# adapter.net
KiCad netlist of a schematic drawn in EAGLE
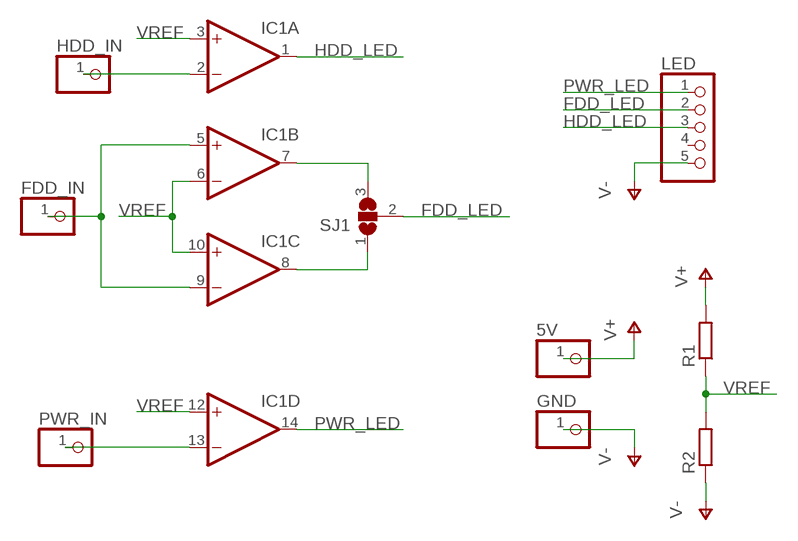
[diagram p0: schematic, sheet 1]

(export (version "E")
  (design (tool "Eeschema 10.0.6"))
  (components
    (comp (ref "5V")
      (value "PINHD-1X1")
      (footprint "eagle-import:1X01")
      (libsource (lib "eagle-import") (part "PINHD-1X1"))
    )
    (comp (ref "FDD_IN")
      (value "PINHD-1X1")
      (footprint "eagle-import:1X01")
      (libsource (lib "eagle-import") (part "PINHD-1X1"))
    )
    (comp (ref "GND")
      (value "PINHD-1X1")
      (footprint "eagle-import:1X01")
      (libsource (lib "eagle-import") (part "PINHD-1X1"))
    )
    (comp (ref "HDD_IN")
      (value "PINHD-1X1")
      (footprint "eagle-import:1X01")
      (libsource (lib "eagle-import") (part "PINHD-1X1"))
    )
    (comp (ref "IC1")
      (value "OP11D")
      (footprint "eagle-import:SO14")
      (libsource (lib "eagle-import") (part "OP11D"))
    )
    (comp (ref "LED")
      (value "PINHD-1X5")
      (footprint "eagle-import:1X05")
      (libsource (lib "eagle-import") (part "PINHD-1X5"))
    )
    (comp (ref "PWR_IN")
      (value "PINHD-1X1")
      (footprint "eagle-import:1X01")
      (libsource (lib "eagle-import") (part "PINHD-1X1"))
    )
    (comp (ref "R1")
      (value "R-EU_R0805")
      (footprint "eagle-import:R0805")
      (libsource (lib "eagle-import") (part "R-EU_R0805"))
    )
    (comp (ref "R2")
      (value "R-EU_R0805")
      (footprint "eagle-import:R0805")
      (libsource (lib "eagle-import") (part "R-EU_R0805"))
    )
    (comp (ref "SJ1")
      (value "SJ2W")
      (footprint "eagle-import:SJ_2")
      (libsource (lib "eagle-import") (part "SJ2W"))
    )
  )
  (nets
    (net (code "1") (name "/FDD_LED") (class "Default")
      (node (ref "LED") (pin "2") (pinfunction "2_2") (pintype "passive"))
      (node (ref "SJ1") (pin "2") (pinfunction "2_2") (pintype "passive"))
    )
    (net (code "2") (name "/HDD_LED") (class "Default")
      (node (ref "IC1") (pin "1") (pinfunction "OUT_1") (pintype "output"))
      (node (ref "LED") (pin "3") (pinfunction "3_3") (pintype "passive"))
    )
    (net (code "3") (name "/PWR_LED") (class "Default")
      (node (ref "IC1") (pin "14") (pinfunction "OUT_14") (pintype "output"))
      (node (ref "LED") (pin "1") (pinfunction "1_1") (pintype "passive"))
    )
    (net (code "4") (name "/VREF") (class "Default")
      (node (ref "IC1") (pin "10") (pinfunction "+IN_10") (pintype "input"))
      (node (ref "IC1") (pin "12") (pinfunction "+IN_12") (pintype "input"))
      (node (ref "IC1") (pin "3") (pinfunction "+IN_3") (pintype "input"))
      (node (ref "IC1") (pin "6") (pinfunction "-IN_6") (pintype "input"))
      (node (ref "R1") (pin "1") (pinfunction "1_1") (pintype "passive"))
      (node (ref "R2") (pin "2") (pinfunction "2_2") (pintype "passive"))
    )
    (net (code "5") (name "Net-(IC1A--IN)") (class "Default")
      (node (ref "HDD_IN") (pin "1") (pinfunction "1_1") (pintype "passive"))
      (node (ref "IC1") (pin "2") (pinfunction "-IN_2") (pintype "input"))
    )
    (net (code "6") (name "Net-(IC1B-+IN)") (class "Default")
      (node (ref "FDD_IN") (pin "1") (pinfunction "1_1") (pintype "passive"))
      (node (ref "IC1") (pin "5") (pinfunction "+IN_5") (pintype "input"))
      (node (ref "IC1") (pin "9") (pinfunction "-IN_9") (pintype "input"))
    )
    (net (code "7") (name "Net-(IC1B-OUT)") (class "Default")
      (node (ref "IC1") (pin "7") (pinfunction "OUT_7") (pintype "output"))
      (node (ref "SJ1") (pin "3") (pinfunction "3_3") (pintype "passive"))
    )
    (net (code "8") (name "Net-(IC1C-OUT)") (class "Default")
      (node (ref "IC1") (pin "8") (pinfunction "OUT_8") (pintype "output"))
      (node (ref "SJ1") (pin "1") (pinfunction "1_1") (pintype "passive"))
    )
    (net (code "9") (name "Net-(IC1D--IN)") (class "Default")
      (node (ref "IC1") (pin "13") (pinfunction "-IN_13") (pintype "input"))
      (node (ref "PWR_IN") (pin "1") (pinfunction "1_1") (pintype "passive"))
    )
    (net (code "10") (name "V+") (class "Default")
      (node (ref "5V") (pin "1") (pinfunction "1_1") (pintype "passive"))
      (node (ref "R1") (pin "2") (pinfunction "2_2") (pintype "passive"))
    )
    (net (code "11") (name "V-") (class "Default")
      (node (ref "GND") (pin "1") (pinfunction "1_1") (pintype "passive"))
      (node (ref "LED") (pin "5") (pinfunction "5_5") (pintype "passive"))
      (node (ref "R2") (pin "1") (pinfunction "1_1") (pintype "passive"))
    )
    (net (code "12") (name "unconnected-(LED-Pad4)") (class "Default")
      (node (ref "LED") (pin "4") (pinfunction "4_4") (pintype "passive"))
    )
  )
)
